# AVD_eFuse_LV_Supply.net
KiCad netlist of a schematic drawn in Altium Designer
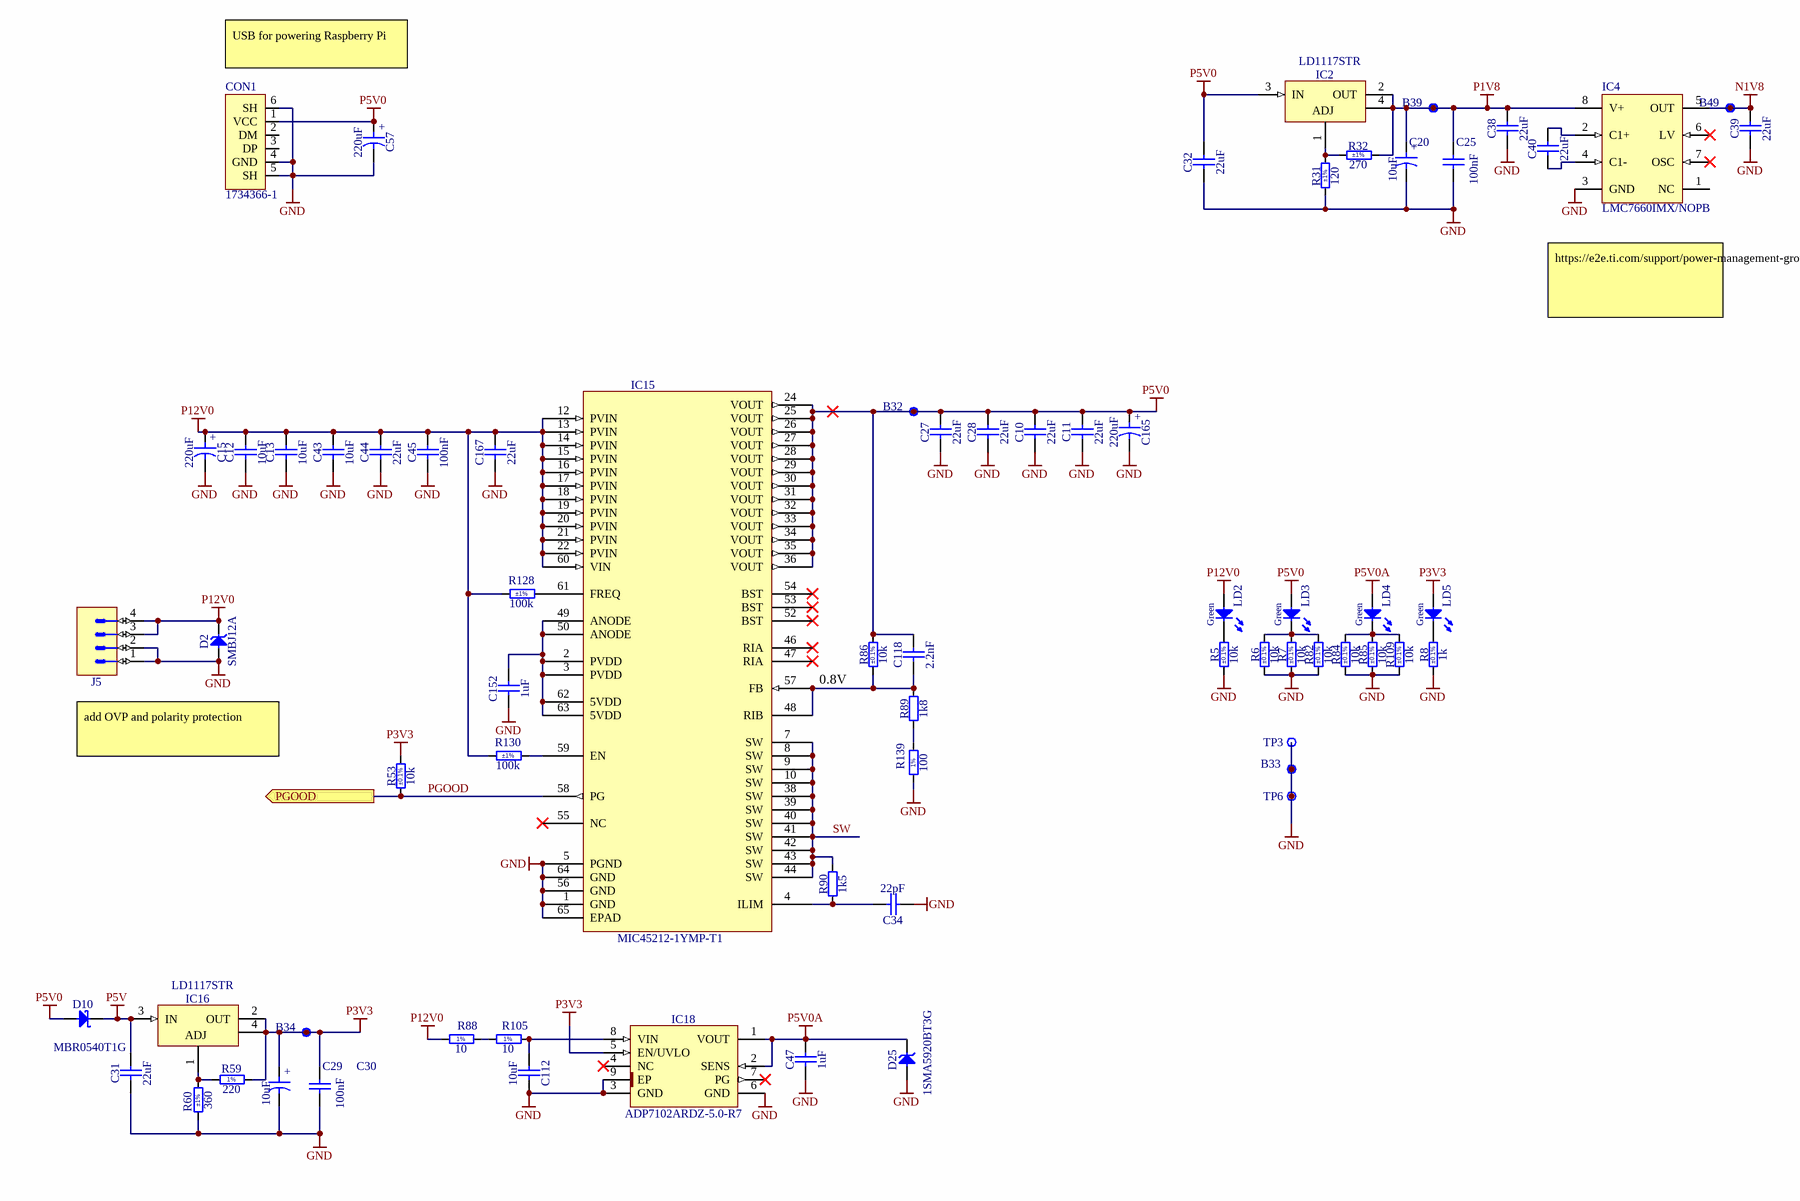
[diagram p0: AVD_eFuse_LV_Supply.SchDoc]

(export (version "E")
  (design (tool "Eeschema 10.0.6"))
  (components
    (comp (ref "B32")
      (value "SMD Pad")
      (footprint "C100")
      (description "Pad")
      (fields (field (name "PART NUMBER") "SMD_PAD_D1MM") (field (name "AUTHOR") "CERN DEM JLC"))
      (libsource (lib "Eletro-mechanical") (part "Single SMD Pad (Round)"))
    )
    (comp (ref "B33")
      (value "SMD Pad")
      (footprint "C100")
      (description "Pad")
      (fields (field (name "PART NUMBER") "SMD_PAD_D1MM") (field (name "AUTHOR") "CERN DEM JLC"))
      (libsource (lib "Eletro-mechanical") (part "Single SMD Pad (Round)"))
    )
    (comp (ref "B34")
      (value "SMD Pad")
      (footprint "C100")
      (description "Pad")
      (fields (field (name "PART NUMBER") "SMD_PAD_D1MM") (field (name "AUTHOR") "CERN DEM JLC"))
      (libsource (lib "Eletro-mechanical") (part "Single SMD Pad (Round)"))
    )
    (comp (ref "B39")
      (value "SMD Pad")
      (footprint "C100")
      (description "Pad")
      (fields (field (name "PART NUMBER") "SMD_PAD_D1MM") (field (name "AUTHOR") "CERN DEM JLC"))
      (libsource (lib "Eletro-mechanical") (part "Single SMD Pad (Round)"))
    )
    (comp (ref "B49")
      (value "SMD Pad")
      (footprint "C100")
      (description "Pad")
      (fields (field (name "PART NUMBER") "SMD_PAD_D1MM") (field (name "AUTHOR") "CERN DEM JLC"))
      (libsource (lib "Eletro-mechanical") (part "Single SMD Pad (Round)"))
    )
    (comp (ref "C10")
      (value "22uF")
      (footprint "CAPC2012X135N")
      (description "Non-polarised capacitor")
      (fields
        (field (name "PART NUMBER") "CC0805_22UF_16V_10%_X5R")
        (field (name "VOLTAGE") "16V")
        (field (name "AUTHOR") "CERN DEM JLC")
      )
      (libsource (lib "Capacitors") (part "Capacitor - non polarized"))
    )
    (comp (ref "C11")
      (value "22uF")
      (footprint "CAPC2012X135N")
      (description "Non-polarised capacitor")
      (fields
        (field (name "PART NUMBER") "CC0805_22UF_16V_10%_X5R")
        (field (name "VOLTAGE") "16V")
        (field (name "AUTHOR") "CERN DEM JLC")
      )
      (libsource (lib "Capacitors") (part "Capacitor - non polarized"))
    )
    (comp (ref "C12")
      (value "10uF")
      (footprint "CAPC2012X135N")
      (description "Non-polarised capacitor")
      (fields
        (field (name "PART NUMBER") "CC0805_10UF_16V_10%_X5R")
        (field (name "VOLTAGE") "16V")
        (field (name "AUTHOR") "CERN DEM JLC")
      )
      (libsource (lib "Capacitors") (part "Capacitor - non polarized"))
    )
    (comp (ref "C13")
      (value "10uF")
      (footprint "CAPC2012X135N")
      (description "Non-polarised capacitor")
      (fields
        (field (name "PART NUMBER") "CC0805_10UF_16V_10%_X5R")
        (field (name "VOLTAGE") "16V")
        (field (name "AUTHOR") "CERN DEM JLC")
      )
      (libsource (lib "Capacitors") (part "Capacitor - non polarized"))
    )
    (comp (ref "C15")
      (value "220uF")
      (footprint "CAPMP7343X430N")
      (description "Polarised capacitor")
      (fields
        (field (name "PART NUMBER") "CTE7343-43_220UF_16V_10%")
        (field (name "VOLTAGE") "16V")
        (field (name "AUTHOR") "CERN DEM JLC")
      )
      (libsource (lib "Capacitors") (part "Capacitor - polarized"))
    )
    (comp (ref "C20")
      (value "10uF")
      (footprint "CAPAE430X540N")
      (description "Polarised capacitor")
      (fields
        (field (name "PART NUMBER") "CAE430-540_10UF_16V_20%")
        (field (name "VOLTAGE") "16V")
        (field (name "AUTHOR") "CERN DEM JLC")
      )
      (libsource (lib "Capacitors") (part "Capacitor - polarized"))
    )
    (comp (ref "C25")
      (value "100nF")
      (footprint "CAPC1608X87N")
      (description "Non-polarised capacitor")
      (fields
        (field (name "PART NUMBER") "CC0603_100NF_50V_10%_X5R")
        (field (name "VOLTAGE") "50V")
        (field (name "AUTHOR") "CERN DEM MR")
      )
      (libsource (lib "Capacitors") (part "Capacitor - non polarized"))
    )
    (comp (ref "C27")
      (value "22uF")
      (footprint "CAPC2012X135N")
      (description "Non-polarised capacitor")
      (fields
        (field (name "PART NUMBER") "CC0805_22UF_16V_10%_X5R")
        (field (name "VOLTAGE") "16V")
        (field (name "AUTHOR") "CERN DEM JLC")
      )
      (libsource (lib "Capacitors") (part "Capacitor - non polarized"))
    )
    (comp (ref "C28")
      (value "22uF")
      (footprint "CAPC2012X135N")
      (description "Non-polarised capacitor")
      (fields
        (field (name "PART NUMBER") "CC0805_22UF_16V_10%_X5R")
        (field (name "VOLTAGE") "16V")
        (field (name "AUTHOR") "CERN DEM JLC")
      )
      (libsource (lib "Capacitors") (part "Capacitor - non polarized"))
    )
    (comp (ref "C29")
      (value "10uF")
      (footprint "CAPAE430X540N")
      (description "Polarised capacitor")
      (fields
        (field (name "PART NUMBER") "CAE430-540_10UF_16V_20%")
        (field (name "VOLTAGE") "16V")
        (field (name "AUTHOR") "CERN DEM JLC")
      )
      (libsource (lib "Capacitors") (part "Capacitor - polarized"))
    )
    (comp (ref "C30")
      (value "100nF")
      (footprint "CAPC1608X87N")
      (description "Non-polarised capacitor")
      (fields
        (field (name "PART NUMBER") "CC0603_100NF_50V_10%_X5R")
        (field (name "VOLTAGE") "50V")
        (field (name "AUTHOR") "CERN DEM MR")
      )
      (libsource (lib "Capacitors") (part "Capacitor - non polarized"))
    )
    (comp (ref "C31")
      (value "22uF")
      (footprint "CAPC2012X135N")
      (description "Non-polarised capacitor")
      (fields
        (field (name "PART NUMBER") "CC0805_22UF_16V_10%_X5R")
        (field (name "VOLTAGE") "16V")
        (field (name "AUTHOR") "CERN DEM JLC")
      )
      (libsource (lib "Capacitors") (part "Capacitor - non polarized"))
    )
    (comp (ref "C32")
      (value "22uF")
      (footprint "CAPC2012X135N")
      (description "Non-polarised capacitor")
      (fields
        (field (name "PART NUMBER") "CC0805_22UF_16V_10%_X5R")
        (field (name "VOLTAGE") "16V")
        (field (name "AUTHOR") "CERN DEM JLC")
      )
      (libsource (lib "Capacitors") (part "Capacitor - non polarized"))
    )
    (comp (ref "C34")
      (value "22pF")
      (footprint "CAPC1005X55N")
      (description "Non-polarised capacitor")
      (fields
        (field (name "PART NUMBER") "CC0402_22PF_50V_5%_C0G")
        (field (name "VOLTAGE") "50V")
        (field (name "AUTHOR") "CERN DEM JLC")
      )
      (libsource (lib "Capacitors") (part "Capacitor - non polarized"))
    )
    (comp (ref "C38")
      (value "22uF")
      (footprint "CAPC2012X135N")
      (description "Non-polarised capacitor")
      (fields
        (field (name "PART NUMBER") "CC0805_22UF_16V_10%_X5R")
        (field (name "VOLTAGE") "16V")
        (field (name "AUTHOR") "CERN DEM JLC")
      )
      (libsource (lib "Capacitors") (part "Capacitor - non polarized"))
    )
    (comp (ref "C39")
      (value "22uF")
      (footprint "CAPC2012X135N")
      (description "Non-polarised capacitor")
      (fields
        (field (name "PART NUMBER") "CC0805_22UF_16V_10%_X5R")
        (field (name "VOLTAGE") "16V")
        (field (name "AUTHOR") "CERN DEM JLC")
      )
      (libsource (lib "Capacitors") (part "Capacitor - non polarized"))
    )
    (comp (ref "C40")
      (value "22uF")
      (footprint "CAPC2012X135N")
      (description "Non-polarised capacitor")
      (fields
        (field (name "PART NUMBER") "CC0805_22UF_16V_10%_X5R")
        (field (name "VOLTAGE") "16V")
        (field (name "AUTHOR") "CERN DEM JLC")
      )
      (libsource (lib "Capacitors") (part "Capacitor - non polarized"))
    )
    (comp (ref "C43")
      (value "10uF")
      (footprint "CAPC2012X135N")
      (description "Non-polarised capacitor")
      (fields
        (field (name "PART NUMBER") "CC0805_10UF_16V_10%_X5R")
        (field (name "VOLTAGE") "16V")
        (field (name "AUTHOR") "CERN DEM JLC")
      )
      (libsource (lib "Capacitors") (part "Capacitor - non polarized"))
    )
    (comp (ref "C44")
      (value "22uF")
      (footprint "CAPC2012X135N")
      (description "Non-polarised capacitor")
      (fields
        (field (name "PART NUMBER") "CC0805_22UF_16V_10%_X5R")
        (field (name "VOLTAGE") "16V")
        (field (name "AUTHOR") "CERN DEM JLC")
      )
      (libsource (lib "Capacitors") (part "Capacitor - non polarized"))
    )
    (comp (ref "C45")
      (value "100nF")
      (footprint "CAPC1608X87N")
      (description "Non-polarised capacitor")
      (fields
        (field (name "PART NUMBER") "CC0603_100NF_50V_10%_X5R")
        (field (name "VOLTAGE") "50V")
        (field (name "AUTHOR") "CERN DEM MR")
      )
      (libsource (lib "Capacitors") (part "Capacitor - non polarized"))
    )
    (comp (ref "C47")
      (value "1uF")
      (footprint "CAPC1608X87N")
      (description "Non-polarised capacitor")
      (fields
        (field (name "PART NUMBER") "CC0603_1UF_25V_10%_X7R")
        (field (name "VOLTAGE") "25V")
        (field (name "AUTHOR") "CERN DEM JLC")
      )
      (libsource (lib "Capacitors") (part "Capacitor - non polarized"))
    )
    (comp (ref "C57")
      (value "220uF")
      (footprint "CAPMP7343X430N")
      (description "Polarised capacitor")
      (fields
        (field (name "PART NUMBER") "CTE7343-43_220UF_16V_10%")
        (field (name "VOLTAGE") "16V")
        (field (name "AUTHOR") "CERN DEM JLC")
      )
      (libsource (lib "Capacitors") (part "Capacitor - polarized"))
    )
    (comp (ref "C112")
      (value "10uF")
      (footprint "CAPC2012X135N")
      (description "Non-polarised capacitor")
      (fields
        (field (name "PART NUMBER") "CC0805_10UF_16V_10%_X5R")
        (field (name "VOLTAGE") "16V")
        (field (name "AUTHOR") "CERN DEM JLC")
      )
      (libsource (lib "Capacitors") (part "Capacitor - non polarized"))
    )
    (comp (ref "C118")
      (value "2.2nF")
      (footprint "CAPC1608X87N")
      (description "Non-polarised capacitor")
      (fields
        (field (name "PART NUMBER") "CC0603_2.2NF_50V_5%_C0G")
        (field (name "VOLTAGE") "50V")
        (field (name "AUTHOR") "CERN DEM JMW")
      )
      (libsource (lib "Capacitors") (part "Capacitor - non polarized"))
    )
    (comp (ref "C152")
      (value "1uF")
      (footprint "CAPC1608X87N")
      (description "Non-polarised capacitor")
      (fields
        (field (name "PART NUMBER") "CC0603_1UF_25V_10%_X7R")
        (field (name "VOLTAGE") "25V")
        (field (name "AUTHOR") "CERN DEM JLC")
      )
      (libsource (lib "Capacitors") (part "Capacitor - non polarized"))
    )
    (comp (ref "C165")
      (value "220uF")
      (footprint "CAPMP7343X430N")
      (description "Polarised capacitor")
      (fields
        (field (name "PART NUMBER") "CTE7343-43_220UF_16V_10%")
        (field (name "VOLTAGE") "16V")
        (field (name "AUTHOR") "CERN DEM JLC")
      )
      (libsource (lib "Capacitors") (part "Capacitor - polarized"))
    )
    (comp (ref "C167")
      (value "22uF")
      (footprint "CAPC2012X135N")
      (description "Non-polarised capacitor")
      (fields
        (field (name "PART NUMBER") "CC0805_22UF_16V_10%_X5R")
        (field (name "VOLTAGE") "16V")
        (field (name "AUTHOR") "CERN DEM JLC")
      )
      (libsource (lib "Capacitors") (part "Capacitor - non polarized"))
    )
    (comp (ref "CON1")
      (value "1734366-1")
      (footprint "1734366-1")
      (description "USB connector A type")
      (libsource (lib "Connectors") (part "CON_USB_A_Vertical"))
    )
    (comp (ref "D2")
      (value "SMBJ12A")
      (footprint "DIOM5336X265N")
      (description "Zener Diode")
      (fields
        (field (name "VOLTAGE") "12V")
        (field (name "POWER") "600W")
        (field (name "AUTHOR") "CERN DEM JLC")
      )
      (libsource (lib "ICs And Semiconductors") (part "Diode Zener"))
    )
    (comp (ref "D10")
      (value "MBR0540T1G")
      (footprint "SOD3716X135N")
      (description "Schottky Diode")
      (fields
        (field (name "VOLTAGE") "40V")
        (field (name "POWER") "500mA")
        (field (name "AUTHOR") "CERN DEM JLC")
      )
      (libsource (lib "ICs And Semiconductors") (part "Diode Schottky"))
    )
    (comp (ref "D25")
      (value "1SMA5920BT3G")
      (footprint "DIOM5226X220N")
      (description "6.2V 1.5 Watt Plastic Surface Mount Zener Voltage Regulators")
      (fields (field (name "VOLTAGE") "6.2V") (field (name "POWER") "1.5W") (field (name "AUTHOR") "GK"))
      (libsource (lib "Diodes") (part "D_Zener_1SMA5920BT3G"))
    )
    (comp (ref "IC2")
      (value "LD1117STR")
      (footprint "SOT230P700X180-4N")
      (description "3-Terminal Regulator 1=Adj 2=OUT 3=IN 4=OUT")
      (fields (field (name "MANUFACTURER") "ST MICROELECTRONICS") (field (name "AUTHOR") "CERN DEM MR"))
      (libsource (lib "ICs And Semiconductors") (part "REG3+1 1ADJ-2OUT-3IN+4OUT"))
    )
    (comp (ref "IC4")
      (value "LMC7660IMX/NOPB")
      (footprint "D0008A_L")
      (description "Switched Capacitor Voltage Converter, 8-pin Narrow SOIC, Pb-Free")
      (fields (field (name "MANUFACTURER") "Texas Instruments"))
      (libsource (lib "Altium Content Vault") (part "PM-CHP-LMC7660IM-8"))
    )
    (comp (ref "IC15")
      (value "MIC45212-1YMP-T1")
      (footprint "MICROCHIP_QFN64_12X12")
      (description "0.8V to 85% PVIN (4.5...26V), 14A Synchronous Step-Down Regulator Module")
      (fields (field (name "MANUFACTURER") "MICROCHIP TECHNOLOGY") (field (name "AUTHOR") "GK"))
      (libsource (lib "Regulators_SMPS") (part "PM_MIC45212-1"))
    )
    (comp (ref "IC16")
      (value "LD1117STR")
      (footprint "SOT230P700X180-4N")
      (description "3-Terminal Regulator 1=Adj 2=OUT 3=IN 4=OUT")
      (fields (field (name "MANUFACTURER") "ST MICROELECTRONICS") (field (name "AUTHOR") "CERN DEM MR"))
      (libsource (lib "ICs And Semiconductors") (part "REG3+1 1ADJ-2OUT-3IN+4OUT"))
    )
    (comp (ref "IC18")
      (value "ADP7102ARDZ-5.0-R7")
      (footprint "SOIC127P600X175-9N-R241X309")
      (description "300 mA, Low Noise, CMOS LDO Linear Regulator")
      (fields (field (name "MANUFACTURER") "ANALOG DEVICES") (field (name "AUTHOR") "CERN DEM JLC"))
      (libsource (lib "ICs And Semiconductors") (part "ADP7102ARDZ-X.X-R7"))
    )
    (comp (ref "J5")
      (value "Mini-Fit Jr.™")
      (footprint "MOLEX_39-30-0040")
      (description "Connector 4 Male")
      (fields
        (field (name "PART NUMBER") "MOLEX_39-30-0040")
        (field (name "MANUFACTURER") "MOLEX")
        (field (name "AUTHOR") "CERN DEM JLC")
      )
      (libsource (lib "Connectors") (part "Connector 4 Male"))
    )
    (comp (ref "LD2")
      (value "Green")
      (footprint "LED_KINGBRIGHT_KP-1608CGCK")
      (description "LED Green 1C 2A")
      (fields
        (field (name "PART NUMBER") "LED_KINGBRIGHT_KP-1608CGCK")
        (field (name "MANUFACTURER") "KINGBRIGHT")
        (field (name "AUTHOR") "CERN DEM HF")
      )
      (libsource (lib "ICs And Semiconductors") (part "LED Green 1C 2A"))
    )
    (comp (ref "LD3")
      (value "Green")
      (footprint "LED_KINGBRIGHT_KP-1608CGCK")
      (description "LED Green 1C 2A")
      (fields
        (field (name "PART NUMBER") "LED_KINGBRIGHT_KP-1608CGCK")
        (field (name "MANUFACTURER") "KINGBRIGHT")
        (field (name "AUTHOR") "CERN DEM HF")
      )
      (libsource (lib "ICs And Semiconductors") (part "LED Green 1C 2A"))
    )
    (comp (ref "LD4")
      (value "Green")
      (footprint "LED_KINGBRIGHT_KP-1608CGCK")
      (description "LED Green 1C 2A")
      (fields
        (field (name "PART NUMBER") "LED_KINGBRIGHT_KP-1608CGCK")
        (field (name "MANUFACTURER") "KINGBRIGHT")
        (field (name "AUTHOR") "CERN DEM HF")
      )
      (libsource (lib "ICs And Semiconductors") (part "LED Green 1C 2A"))
    )
    (comp (ref "LD5")
      (value "Green")
      (footprint "LED_KINGBRIGHT_KP-1608CGCK")
      (description "LED Green 1C 2A")
      (fields
        (field (name "PART NUMBER") "LED_KINGBRIGHT_KP-1608CGCK")
        (field (name "MANUFACTURER") "KINGBRIGHT")
        (field (name "AUTHOR") "CERN DEM HF")
      )
      (libsource (lib "ICs And Semiconductors") (part "LED Green 1C 2A"))
    )
    (comp (ref "R5")
      (value "10k")
      (footprint "RESC1608X64N")
      (description "Resistor - 0.1%")
      (fields
        (field (name "TOLERANCE") "±0.1%")
        (field (name "PART NUMBER") "R0603_10K_0.1%_0.1W_25PPM")
        (field (name "POWER") "0.1W")
        (field (name "AUTHOR") "CERN DEM JMW")
      )
      (libsource (lib "Resistors") (part "Resistor - 0.1%"))
    )
    (comp (ref "R6")
      (value "10k")
      (footprint "RESC1608X64N")
      (description "Resistor - 0.1%")
      (fields
        (field (name "TOLERANCE") "±0.1%")
        (field (name "PART NUMBER") "R0603_10K_0.1%_0.1W_25PPM")
        (field (name "POWER") "0.1W")
        (field (name "AUTHOR") "CERN DEM JMW")
      )
      (libsource (lib "Resistors") (part "Resistor - 0.1%"))
    )
    (comp (ref "R7")
      (value "10k")
      (footprint "RESC1608X64N")
      (description "Resistor - 0.1%")
      (fields
        (field (name "TOLERANCE") "±0.1%")
        (field (name "PART NUMBER") "R0603_10K_0.1%_0.1W_25PPM")
        (field (name "POWER") "0.1W")
        (field (name "AUTHOR") "CERN DEM JMW")
      )
      (libsource (lib "Resistors") (part "Resistor - 0.1%"))
    )
    (comp (ref "R8")
      (value "1k")
      (footprint "RESC1608X55N")
      (description "Resistor - 0.1%")
      (fields
        (field (name "TOLERANCE") "±0.1%")
        (field (name "PART NUMBER") "R0603_1K_0.1%_0.063W_10PPM")
        (field (name "POWER") "0.063W")
        (field (name "AUTHOR") "CERN DEM BC")
      )
      (libsource (lib "Resistors") (part "Resistor - 0.1%"))
    )
    (comp (ref "R31")
      (value "120")
      (footprint "RESC1005X40N")
      (description "Resistor - 1%")
      (fields
        (field (name "TOLERANCE") "±1%")
        (field (name "PART NUMBER") "R0402_120R_1%_0.0625W_100PPM")
        (field (name "POWER") "0.0625W")
        (field (name "AUTHOR") "CERN DEM JLC")
      )
      (libsource (lib "Resistors") (part "Resistor - 1%"))
    )
    (comp (ref "R32")
      (value "270")
      (footprint "RESC1005X40N")
      (description "Resistor - 1%")
      (fields
        (field (name "TOLERANCE") "±1%")
        (field (name "PART NUMBER") "R0402_270R_1%_0.0625W_100PPM")
        (field (name "POWER") "0.0625W")
        (field (name "AUTHOR") "CERN DEM JLC")
      )
      (libsource (lib "Resistors") (part "Resistor - 1%"))
    )
    (comp (ref "R53")
      (value "10k")
      (footprint "RESC1608X64N")
      (description "Resistor - 0.1%")
      (fields
        (field (name "TOLERANCE") "±0.1%")
        (field (name "PART NUMBER") "R0603_10K_0.1%_0.1W_25PPM")
        (field (name "POWER") "0.1W")
        (field (name "AUTHOR") "CERN DEM JMW")
      )
      (libsource (lib "Resistors") (part "Resistor - 0.1%"))
    )
    (comp (ref "R59")
      (value "220")
      (footprint "RESC1005X40N")
      (description "Resistor - 1%")
      (fields
        (field (name "PART NUMBER") "R0402_220R_1%_0.0625W_100PPM")
        (field (name "POWER") "0.0625W")
        (field (name "AUTHOR") "CERN DEM JLC")
      )
      (libsource (lib "") (part "Resistor - 1%_1"))
    )
    (comp (ref "R60")
      (value "360")
      (footprint "RESC1608X55N")
      (description "Resistor - 1%")
      (fields
        (field (name "TOLERANCE") "±1%")
        (field (name "PART NUMBER") "R0603_360R_1%_0.1W_100PPM")
        (field (name "POWER") "0.1W")
        (field (name "AUTHOR") "CERN DEM JLC")
      )
      (libsource (lib "Resistors") (part "Resistor - 1%"))
    )
    (comp (ref "R82")
      (value "10k")
      (footprint "RESC1608X64N")
      (description "Resistor - 0.1%")
      (fields
        (field (name "TOLERANCE") "±0.1%")
        (field (name "PART NUMBER") "R0603_10K_0.1%_0.1W_25PPM")
        (field (name "POWER") "0.1W")
        (field (name "AUTHOR") "CERN DEM JMW")
      )
      (libsource (lib "Resistors") (part "Resistor - 0.1%"))
    )
    (comp (ref "R84")
      (value "10k")
      (footprint "RESC1608X64N")
      (description "Resistor - 0.1%")
      (fields
        (field (name "TOLERANCE") "±0.1%")
        (field (name "PART NUMBER") "R0603_10K_0.1%_0.1W_25PPM")
        (field (name "POWER") "0.1W")
        (field (name "AUTHOR") "CERN DEM JMW")
      )
      (libsource (lib "Resistors") (part "Resistor - 0.1%"))
    )
    (comp (ref "R85")
      (value "10k")
      (footprint "RESC1608X64N")
      (description "Resistor - 0.1%")
      (fields
        (field (name "TOLERANCE") "±0.1%")
        (field (name "PART NUMBER") "R0603_10K_0.1%_0.1W_25PPM")
        (field (name "POWER") "0.1W")
        (field (name "AUTHOR") "CERN DEM JMW")
      )
      (libsource (lib "Resistors") (part "Resistor - 0.1%"))
    )
    (comp (ref "R86")
      (value "10k")
      (footprint "RESC1608X64N")
      (description "Resistor - 0.1%")
      (fields
        (field (name "TOLERANCE") "±0.1%")
        (field (name "PART NUMBER") "R0603_10K_0.1%_0.1W_25PPM")
        (field (name "POWER") "0.1W")
        (field (name "AUTHOR") "CERN DEM JMW")
      )
      (libsource (lib "Resistors") (part "Resistor - 0.1%"))
    )
    (comp (ref "R88")
      (value "10")
      (footprint "RESC2012X60N")
      (description "Resistor - 1%")
      (fields
        (field (name "PART NUMBER") "R0805_10R_1%_0.125W_200PPM")
        (field (name "POWER") "0.125W")
        (field (name "AUTHOR") "CERN DEM JLC")
      )
      (libsource (lib "") (part "Resistor - 1%_1"))
    )
    (comp (ref "R89")
      (value "1k8")
      (footprint "RESC1608X55N")
      (description "Resistor - 1%")
      (fields
        (field (name "PART NUMBER") "R0603_1K8_1%_0.1W_100PPM")
        (field (name "POWER") "0.1W")
        (field (name "AUTHOR") "CERN DEM JLC")
      )
      (libsource (lib "Resistors") (part "Resistor - 1%"))
    )
    (comp (ref "R90")
      (value "1k5")
      (footprint "RESC1005X40N")
      (description "Resistor - 1%")
      (fields
        (field (name "PART NUMBER") "R0402_1K5_1%_0.0625W_100PPM")
        (field (name "POWER") "0.0625W")
        (field (name "AUTHOR") "CERN DEM JLC")
      )
      (libsource (lib "Resistors") (part "Resistor - 1%"))
    )
    (comp (ref "R105")
      (value "10")
      (footprint "RESC2012X60N")
      (description "Resistor - 1%")
      (fields
        (field (name "PART NUMBER") "R0805_10R_1%_0.125W_200PPM")
        (field (name "POWER") "0.125W")
        (field (name "AUTHOR") "CERN DEM JLC")
      )
      (libsource (lib "") (part "Resistor - 1%_1"))
    )
    (comp (ref "R109")
      (value "10k")
      (footprint "RESC1608X64N")
      (description "Resistor - 0.1%")
      (fields
        (field (name "TOLERANCE") "±0.1%")
        (field (name "PART NUMBER") "R0603_10K_0.1%_0.1W_25PPM")
        (field (name "POWER") "0.1W")
        (field (name "AUTHOR") "CERN DEM JMW")
      )
      (libsource (lib "Resistors") (part "Resistor - 0.1%"))
    )
    (comp (ref "R128")
      (value "100k")
      (footprint "RESC1608X55N")
      (description "Resistor - 1%")
      (fields
        (field (name "TOLERANCE") "±1%")
        (field (name "PART NUMBER") "R0603_100K_1%_0.1W_100PPM")
        (field (name "POWER") "0.1W")
        (field (name "AUTHOR") "CERN DEM JLC")
      )
      (libsource (lib "Resistors") (part "Resistor - 1%"))
    )
    (comp (ref "R130")
      (value "100k")
      (footprint "RESC1608X55N")
      (description "Resistor - 1%")
      (fields
        (field (name "TOLERANCE") "±1%")
        (field (name "PART NUMBER") "R0603_100K_1%_0.1W_100PPM")
        (field (name "POWER") "0.1W")
        (field (name "AUTHOR") "CERN DEM JLC")
      )
      (libsource (lib "Resistors") (part "Resistor - 1%"))
    )
    (comp (ref "R139")
      (value "100")
      (footprint "RESC1005X40N")
      (description "Resistor - 1%")
      (fields
        (field (name "PART NUMBER") "R0402_100R_1%_0.0625W_100PPM")
        (field (name "POWER") "0.0625W")
        (field (name "AUTHOR") "CERN DEM JLC")
      )
      (libsource (lib "") (part "Resistor - 1%_1"))
    )
    (comp (ref "TP3")
      (value "~")
      (footprint "TYCO_RCT-0C")
      (description "Test Point")
      (fields
        (field (name "PART NUMBER") "TYCO_RCT-0C")
        (field (name "MANUFACTURER") "TYCO ELECTRONICS")
        (field (name "AUTHOR") "CERN DEM JLC")
      )
      (libsource (lib "Connectors") (part "Test Point"))
    )
    (comp (ref "TP6")
      (value "~")
      (footprint "TYCO_RCT-0C")
      (description "Test Point")
      (fields
        (field (name "PART NUMBER") "TYCO_RCT-0C")
        (field (name "MANUFACTURER") "TYCO ELECTRONICS")
        (field (name "AUTHOR") "CERN DEM JLC")
      )
      (libsource (lib "Connectors") (part "Test Point"))
    )
  )
  (nets
    (net (code "1") (name "/PGOOD") (class "Default")
      (node (ref "IC15") (pin "58") (pinfunction "PG_58") (pintype "output"))
      (node (ref "R53") (pin "1") (pinfunction "1_1") (pintype "passive"))
    )
    (net (code "2") (name "/SW") (class "Default")
      (node (ref "IC15") (pin "10") (pinfunction "SW_10") (pintype "passive"))
      (node (ref "IC15") (pin "38") (pinfunction "SW_38") (pintype "passive"))
      (node (ref "IC15") (pin "39") (pinfunction "SW_39") (pintype "passive"))
      (node (ref "IC15") (pin "40") (pinfunction "SW_40") (pintype "passive"))
      (node (ref "IC15") (pin "41") (pinfunction "SW_41") (pintype "passive"))
      (node (ref "IC15") (pin "42") (pinfunction "SW_42") (pintype "passive"))
      (node (ref "IC15") (pin "43") (pinfunction "SW_43") (pintype "passive"))
      (node (ref "IC15") (pin "44") (pinfunction "SW_44") (pintype "passive"))
      (node (ref "IC15") (pin "7") (pinfunction "SW_7") (pintype "passive"))
      (node (ref "IC15") (pin "8") (pinfunction "SW_8") (pintype "passive"))
      (node (ref "IC15") (pin "9") (pinfunction "SW_9") (pintype "passive"))
      (node (ref "R90") (pin "2") (pinfunction "2_2") (pintype "passive"))
    )
    (net (code "3") (name "GND") (class "Default")
      (node (ref "B33") (pin "1") (pinfunction "1_1") (pintype "bidirectional"))
      (node (ref "C10") (pin "1") (pinfunction "1_1") (pintype "passive"))
      (node (ref "C11") (pin "1") (pinfunction "1_1") (pintype "passive"))
      (node (ref "C112") (pin "2") (pinfunction "2_2") (pintype "passive"))
      (node (ref "C12") (pin "1") (pinfunction "1_1") (pintype "passive"))
      (node (ref "C13") (pin "1") (pinfunction "1_1") (pintype "passive"))
      (node (ref "C15") (pin "2") (pinfunction "2_2") (pintype "passive"))
      (node (ref "C152") (pin "1") (pinfunction "1_1") (pintype "passive"))
      (node (ref "C165") (pin "2") (pinfunction "2_2") (pintype "passive"))
      (node (ref "C167") (pin "1") (pinfunction "1_1") (pintype "passive"))
      (node (ref "C20") (pin "2") (pinfunction "2_2") (pintype "passive"))
      (node (ref "C25") (pin "1") (pinfunction "1_1") (pintype "passive"))
      (node (ref "C27") (pin "1") (pinfunction "1_1") (pintype "passive"))
      (node (ref "C28") (pin "1") (pinfunction "1_1") (pintype "passive"))
      (node (ref "C29") (pin "2") (pinfunction "2_2") (pintype "passive"))
      (node (ref "C30") (pin "1") (pinfunction "1_1") (pintype "passive"))
      (node (ref "C31") (pin "1") (pinfunction "1_1") (pintype "passive"))
      (node (ref "C32") (pin "1") (pinfunction "1_1") (pintype "passive"))
      (node (ref "C34") (pin "1") (pinfunction "1_1") (pintype "passive"))
      (node (ref "C38") (pin "1") (pinfunction "1_1") (pintype "passive"))
      (node (ref "C39") (pin "1") (pinfunction "1_1") (pintype "passive"))
      (node (ref "C43") (pin "1") (pinfunction "1_1") (pintype "passive"))
      (node (ref "C44") (pin "1") (pinfunction "1_1") (pintype "passive"))
      (node (ref "C45") (pin "1") (pinfunction "1_1") (pintype "passive"))
      (node (ref "C47") (pin "1") (pinfunction "1_1") (pintype "passive"))
      (node (ref "C57") (pin "2") (pinfunction "2_2") (pintype "passive"))
      (node (ref "CON1") (pin "4") (pinfunction "GND_4") (pintype "passive"))
      (node (ref "CON1") (pin "5") (pinfunction "SH_5") (pintype "passive"))
      (node (ref "CON1") (pin "6") (pinfunction "SH_6") (pintype "passive"))
      (node (ref "D2") (pin "2") (pinfunction "A_2") (pintype "passive"))
      (node (ref "D25") (pin "2") (pinfunction "A_2") (pintype "passive"))
      (node (ref "IC15") (pin "1") (pinfunction "GND_1") (pintype "power_in"))
      (node (ref "IC15") (pin "5") (pinfunction "PGND_5") (pintype "power_in"))
      (node (ref "IC15") (pin "56") (pinfunction "GND_56") (pintype "power_in"))
      (node (ref "IC15") (pin "64") (pinfunction "GND_64") (pintype "power_in"))
      (node (ref "IC15") (pin "65") (pinfunction "EPAD_65") (pintype "power_in"))
      (node (ref "IC18") (pin "3") (pinfunction "GND_3") (pintype "power_in"))
      (node (ref "IC18") (pin "6") (pinfunction "GND_6") (pintype "power_in"))
      (node (ref "IC18") (pin "9") (pinfunction "EP_9") (pintype "power_in"))
      (node (ref "IC4") (pin "3") (pinfunction "GND_3") (pintype "power_in"))
      (node (ref "J5") (pin "1") (pinfunction "1_1") (pintype "bidirectional"))
      (node (ref "J5") (pin "2") (pinfunction "2_2") (pintype "bidirectional"))
      (node (ref "R109") (pin "1") (pinfunction "1_1") (pintype "passive"))
      (node (ref "R139") (pin "1") (pinfunction "1_1") (pintype "passive"))
      (node (ref "R31") (pin "1") (pinfunction "1_1") (pintype "passive"))
      (node (ref "R5") (pin "1") (pinfunction "1_1") (pintype "passive"))
      (node (ref "R6") (pin "1") (pinfunction "1_1") (pintype "passive"))
      (node (ref "R60") (pin "1") (pinfunction "1_1") (pintype "passive"))
      (node (ref "R7") (pin "1") (pinfunction "1_1") (pintype "passive"))
      (node (ref "R8") (pin "1") (pinfunction "1_1") (pintype "passive"))
      (node (ref "R82") (pin "1") (pinfunction "1_1") (pintype "passive"))
      (node (ref "R84") (pin "1") (pinfunction "1_1") (pintype "passive"))
      (node (ref "R85") (pin "1") (pinfunction "1_1") (pintype "passive"))
      (node (ref "TP3") (pin "1") (pinfunction "1_1") (pintype "bidirectional"))
      (node (ref "TP6") (pin "1") (pinfunction "1_1") (pintype "bidirectional"))
    )
    (net (code "4") (name "N1V8") (class "Default")
      (node (ref "B49") (pin "1") (pinfunction "1_1") (pintype "bidirectional"))
      (node (ref "C39") (pin "2") (pinfunction "2_2") (pintype "passive"))
      (node (ref "IC4") (pin "5") (pinfunction "OUT_5") (pintype "power_in"))
    )
    (net (code "5") (name "Net-(C152-Pad2)") (class "Default")
      (node (ref "C152") (pin "2") (pinfunction "2_2") (pintype "passive"))
      (node (ref "IC15") (pin "2") (pinfunction "PVDD_2") (pintype "power_in"))
      (node (ref "IC15") (pin "3") (pinfunction "PVDD_3") (pintype "power_in"))
      (node (ref "IC15") (pin "49") (pinfunction "ANODE_49") (pintype "passive"))
      (node (ref "IC15") (pin "50") (pinfunction "ANODE_50") (pintype "passive"))
      (node (ref "IC15") (pin "62") (pinfunction "5VDD_62") (pintype "power_in"))
      (node (ref "IC15") (pin "63") (pinfunction "5VDD_63") (pintype "power_in"))
    )
    (net (code "6") (name "Net-(IC2-ADJ)") (class "Default")
      (node (ref "IC2") (pin "1") (pinfunction "ADJ_1") (pintype "power_in"))
      (node (ref "R31") (pin "2") (pinfunction "2_2") (pintype "passive"))
      (node (ref "R32") (pin "1") (pinfunction "1_1") (pintype "passive"))
    )
    (net (code "7") (name "Net-(IC4-C1+)") (class "Default")
      (node (ref "C40") (pin "2") (pinfunction "2_2") (pintype "passive"))
      (node (ref "IC4") (pin "2") (pinfunction "C1+_2") (pintype "input"))
    )
    (net (code "8") (name "Net-(IC4-C1-)") (class "Default")
      (node (ref "C40") (pin "1") (pinfunction "1_1") (pintype "passive"))
      (node (ref "IC4") (pin "4") (pinfunction "C1-_4") (pintype "input"))
    )
    (net (code "9") (name "Net-(IC15-EN)") (class "Default")
      (node (ref "IC15") (pin "59") (pinfunction "EN_59") (pintype "passive"))
      (node (ref "R130") (pin "2") (pinfunction "2_2") (pintype "passive"))
    )
    (net (code "10") (name "Net-(IC15-FB)") (class "Default")
      (node (ref "C118") (pin "1") (pinfunction "1_1") (pintype "passive"))
      (node (ref "IC15") (pin "48") (pinfunction "RIB_48") (pintype "passive"))
      (node (ref "IC15") (pin "57") (pinfunction "FB_57") (pintype "input"))
      (node (ref "R86") (pin "1") (pinfunction "1_1") (pintype "passive"))
      (node (ref "R89") (pin "2") (pinfunction "2_2") (pintype "passive"))
    )
    (net (code "11") (name "Net-(IC15-FREQ)") (class "Default")
      (node (ref "IC15") (pin "61") (pinfunction "FREQ_61") (pintype "passive"))
      (node (ref "R128") (pin "2") (pinfunction "2_2") (pintype "passive"))
    )
    (net (code "12") (name "Net-(IC15-ILIM)") (class "Default")
      (node (ref "C34") (pin "2") (pinfunction "2_2") (pintype "passive"))
      (node (ref "IC15") (pin "4") (pinfunction "ILIM_4") (pintype "passive"))
      (node (ref "R90") (pin "1") (pinfunction "1_1") (pintype "passive"))
    )
    (net (code "13") (name "Net-(IC16-ADJ)") (class "Default")
      (node (ref "IC16") (pin "1") (pinfunction "ADJ_1") (pintype "power_in"))
      (node (ref "R59") (pin "1") (pinfunction "1_1") (pintype "passive"))
      (node (ref "R60") (pin "2") (pinfunction "2_2") (pintype "passive"))
    )
    (net (code "14") (name "Net-(IC18-VIN)") (class "Default")
      (node (ref "C112") (pin "1") (pinfunction "1_1") (pintype "passive"))
      (node (ref "IC18") (pin "8") (pinfunction "VIN_8") (pintype "input"))
      (node (ref "R105") (pin "2") (pinfunction "2_2") (pintype "passive"))
    )
    (net (code "15") (name "Net-(LD2-C)") (class "Default")
      (node (ref "LD2") (pin "1") (pinfunction "C_1") (pintype "passive"))
      (node (ref "R5") (pin "2") (pinfunction "2_2") (pintype "passive"))
    )
    (net (code "16") (name "Net-(LD3-C)") (class "Default")
      (node (ref "LD3") (pin "1") (pinfunction "C_1") (pintype "passive"))
      (node (ref "R6") (pin "2") (pinfunction "2_2") (pintype "passive"))
      (node (ref "R7") (pin "2") (pinfunction "2_2") (pintype "passive"))
      (node (ref "R82") (pin "2") (pinfunction "2_2") (pintype "passive"))
    )
    (net (code "17") (name "Net-(LD4-C)") (class "Default")
      (node (ref "LD4") (pin "1") (pinfunction "C_1") (pintype "passive"))
      (node (ref "R109") (pin "2") (pinfunction "2_2") (pintype "passive"))
      (node (ref "R84") (pin "2") (pinfunction "2_2") (pintype "passive"))
      (node (ref "R85") (pin "2") (pinfunction "2_2") (pintype "passive"))
    )
    (net (code "18") (name "Net-(LD5-C)") (class "Default")
      (node (ref "LD5") (pin "1") (pinfunction "C_1") (pintype "passive"))
      (node (ref "R8") (pin "2") (pinfunction "2_2") (pintype "passive"))
    )
    (net (code "19") (name "Net-(R105-Pad1)") (class "Default")
      (node (ref "R105") (pin "1") (pinfunction "1_1") (pintype "passive"))
      (node (ref "R88") (pin "2") (pinfunction "2_2") (pintype "passive"))
    )
    (net (code "20") (name "Net-(R139-Pad2)") (class "Default")
      (node (ref "R139") (pin "2") (pinfunction "2_2") (pintype "passive"))
      (node (ref "R89") (pin "1") (pinfunction "1_1") (pintype "passive"))
    )
    (net (code "21") (name "P1V8") (class "Default")
      (node (ref "B39") (pin "1") (pinfunction "1_1") (pintype "bidirectional"))
      (node (ref "C20") (pin "1") (pinfunction "1_1") (pintype "passive"))
      (node (ref "C25") (pin "2") (pinfunction "2_2") (pintype "passive"))
      (node (ref "C38") (pin "2") (pinfunction "2_2") (pintype "passive"))
      (node (ref "IC2") (pin "2") (pinfunction "OUT_2") (pintype "power_in"))
      (node (ref "IC2") (pin "4") (pinfunction "OUT_4") (pintype "power_in"))
      (node (ref "IC4") (pin "8") (pinfunction "V+_8") (pintype "power_in"))
      (node (ref "R32") (pin "2") (pinfunction "2_2") (pintype "passive"))
    )
    (net (code "22") (name "P3V3") (class "Default")
      (node (ref "B34") (pin "1") (pinfunction "1_1") (pintype "bidirectional"))
      (node (ref "C29") (pin "1") (pinfunction "1_1") (pintype "passive"))
      (node (ref "C30") (pin "2") (pinfunction "2_2") (pintype "passive"))
      (node (ref "IC16") (pin "2") (pinfunction "OUT_2") (pintype "power_in"))
      (node (ref "IC16") (pin "4") (pinfunction "OUT_4") (pintype "power_in"))
      (node (ref "IC18") (pin "5") (pinfunction "EN/UVLO_5") (pintype "input"))
      (node (ref "LD5") (pin "2") (pinfunction "A_2") (pintype "passive"))
      (node (ref "R53") (pin "2") (pinfunction "2_2") (pintype "passive"))
      (node (ref "R59") (pin "2") (pinfunction "2_2") (pintype "passive"))
    )
    (net (code "23") (name "P5V") (class "Default")
      (node (ref "C31") (pin "2") (pinfunction "2_2") (pintype "passive"))
      (node (ref "D10") (pin "1") (pinfunction "C_1") (pintype "passive"))
      (node (ref "IC16") (pin "3") (pinfunction "IN_3") (pintype "input"))
    )
    (net (code "24") (name "P5V0") (class "Default")
      (node (ref "B32") (pin "1") (pinfunction "1_1") (pintype "bidirectional"))
      (node (ref "C10") (pin "2") (pinfunction "2_2") (pintype "passive"))
      (node (ref "C11") (pin "2") (pinfunction "2_2") (pintype "passive"))
      (node (ref "C118") (pin "2") (pinfunction "2_2") (pintype "passive"))
      (node (ref "C165") (pin "1") (pinfunction "1_1") (pintype "passive"))
      (node (ref "C27") (pin "2") (pinfunction "2_2") (pintype "passive"))
      (node (ref "C28") (pin "2") (pinfunction "2_2") (pintype "passive"))
      (node (ref "C32") (pin "2") (pinfunction "2_2") (pintype "passive"))
      (node (ref "C57") (pin "1") (pinfunction "1_1") (pintype "passive"))
      (node (ref "CON1") (pin "1") (pinfunction "VCC_1") (pintype "passive"))
      (node (ref "D10") (pin "2") (pinfunction "A_2") (pintype "passive"))
      (node (ref "IC15") (pin "24") (pinfunction "VOUT_24") (pintype "output"))
      (node (ref "IC15") (pin "25") (pinfunction "VOUT_25") (pintype "output"))
      (node (ref "IC15") (pin "26") (pinfunction "VOUT_26") (pintype "output"))
      (node (ref "IC15") (pin "27") (pinfunction "VOUT_27") (pintype "output"))
      (node (ref "IC15") (pin "28") (pinfunction "VOUT_28") (pintype "output"))
      (node (ref "IC15") (pin "29") (pinfunction "VOUT_29") (pintype "output"))
      (node (ref "IC15") (pin "30") (pinfunction "VOUT_30") (pintype "output"))
      (node (ref "IC15") (pin "31") (pinfunction "VOUT_31") (pintype "output"))
      (node (ref "IC15") (pin "32") (pinfunction "VOUT_32") (pintype "output"))
      (node (ref "IC15") (pin "33") (pinfunction "VOUT_33") (pintype "output"))
      (node (ref "IC15") (pin "34") (pinfunction "VOUT_34") (pintype "output"))
      (node (ref "IC15") (pin "35") (pinfunction "VOUT_35") (pintype "output"))
      (node (ref "IC15") (pin "36") (pinfunction "VOUT_36") (pintype "output"))
      (node (ref "IC2") (pin "3") (pinfunction "IN_3") (pintype "input"))
      (node (ref "LD3") (pin "2") (pinfunction "A_2") (pintype "passive"))
      (node (ref "R86") (pin "2") (pinfunction "2_2") (pintype "passive"))
    )
    (net (code "25") (name "P5V0A") (class "Default")
      (node (ref "C47") (pin "2") (pinfunction "2_2") (pintype "passive"))
      (node (ref "D25") (pin "1") (pinfunction "C_1") (pintype "passive"))
      (node (ref "IC18") (pin "1") (pinfunction "VOUT_1") (pintype "power_in"))
      (node (ref "IC18") (pin "2") (pinfunction "SENS_2") (pintype "input"))
      (node (ref "LD4") (pin "2") (pinfunction "A_2") (pintype "passive"))
    )
    (net (code "26") (name "P12V0") (class "Default")
      (node (ref "C12") (pin "2") (pinfunction "2_2") (pintype "passive"))
      (node (ref "C13") (pin "2") (pinfunction "2_2") (pintype "passive"))
      (node (ref "C15") (pin "1") (pinfunction "1_1") (pintype "passive"))
      (node (ref "C167") (pin "2") (pinfunction "2_2") (pintype "passive"))
      (node (ref "C43") (pin "2") (pinfunction "2_2") (pintype "passive"))
      (node (ref "C44") (pin "2") (pinfunction "2_2") (pintype "passive"))
      (node (ref "C45") (pin "2") (pinfunction "2_2") (pintype "passive"))
      (node (ref "D2") (pin "1") (pinfunction "C_1") (pintype "passive"))
      (node (ref "IC15") (pin "12") (pinfunction "PVIN_12") (pintype "input"))
      (node (ref "IC15") (pin "13") (pinfunction "PVIN_13") (pintype "input"))
      (node (ref "IC15") (pin "14") (pinfunction "PVIN_14") (pintype "input"))
      (node (ref "IC15") (pin "15") (pinfunction "PVIN_15") (pintype "input"))
      (node (ref "IC15") (pin "16") (pinfunction "PVIN_16") (pintype "input"))
      (node (ref "IC15") (pin "17") (pinfunction "PVIN_17") (pintype "input"))
      (node (ref "IC15") (pin "18") (pinfunction "PVIN_18") (pintype "input"))
      (node (ref "IC15") (pin "19") (pinfunction "PVIN_19") (pintype "input"))
      (node (ref "IC15") (pin "20") (pinfunction "PVIN_20") (pintype "input"))
      (node (ref "IC15") (pin "21") (pinfunction "PVIN_21") (pintype "input"))
      (node (ref "IC15") (pin "22") (pinfunction "PVIN_22") (pintype "input"))
      (node (ref "IC15") (pin "60") (pinfunction "VIN_60") (pintype "input"))
      (node (ref "J5") (pin "3") (pinfunction "3_3") (pintype "bidirectional"))
      (node (ref "J5") (pin "4") (pinfunction "4_4") (pintype "bidirectional"))
      (node (ref "LD2") (pin "2") (pinfunction "A_2") (pintype "passive"))
      (node (ref "R128") (pin "1") (pinfunction "1_1") (pintype "passive"))
      (node (ref "R130") (pin "1") (pinfunction "1_1") (pintype "passive"))
      (node (ref "R88") (pin "1") (pinfunction "1_1") (pintype "passive"))
    )
    (net (code "27") (name "unconnected-(CON1-DM-Pad2)") (class "Default")
      (node (ref "CON1") (pin "2") (pinfunction "DM_2") (pintype "passive"))
    )
    (net (code "28") (name "unconnected-(CON1-DP-Pad3)") (class "Default")
      (node (ref "CON1") (pin "3") (pinfunction "DP_3") (pintype "passive"))
    )
    (net (code "29") (name "unconnected-(IC4-LV-Pad6)") (class "Default")
      (node (ref "IC4") (pin "6") (pinfunction "LV_6") (pintype "input+no_connect"))
    )
    (net (code "30") (name "unconnected-(IC4-NC-Pad1)") (class "Default")
      (node (ref "IC4") (pin "1") (pinfunction "NC_1") (pintype "passive"))
    )
    (net (code "31") (name "unconnected-(IC4-OSC-Pad7)") (class "Default")
      (node (ref "IC4") (pin "7") (pinfunction "OSC_7") (pintype "input+no_connect"))
    )
    (net (code "32") (name "unconnected-(IC15-BST-Pad52)") (class "Default")
      (node (ref "IC15") (pin "52") (pinfunction "BST_52") (pintype "passive+no_connect"))
    )
    (net (code "33") (name "unconnected-(IC15-BST-Pad53)") (class "Default")
      (node (ref "IC15") (pin "53") (pinfunction "BST_53") (pintype "passive+no_connect"))
    )
    (net (code "34") (name "unconnected-(IC15-BST-Pad54)") (class "Default")
      (node (ref "IC15") (pin "54") (pinfunction "BST_54") (pintype "passive+no_connect"))
    )
    (net (code "35") (name "unconnected-(IC15-NC-Pad55)") (class "Default")
      (node (ref "IC15") (pin "55") (pinfunction "NC_55") (pintype "passive+no_connect"))
    )
    (net (code "36") (name "unconnected-(IC15-RIA-Pad46)") (class "Default")
      (node (ref "IC15") (pin "46") (pinfunction "RIA_46") (pintype "passive+no_connect"))
    )
    (net (code "37") (name "unconnected-(IC15-RIA-Pad47)") (class "Default")
      (node (ref "IC15") (pin "47") (pinfunction "RIA_47") (pintype "passive+no_connect"))
    )
    (net (code "38") (name "unconnected-(IC18-NC-Pad4)") (class "Default")
      (node (ref "IC18") (pin "4") (pinfunction "NC_4") (pintype "passive+no_connect"))
    )
    (net (code "39") (name "unconnected-(IC18-PG-Pad7)") (class "Default")
      (node (ref "IC18") (pin "7") (pinfunction "PG_7") (pintype "output+no_connect"))
    )
  )
)
